# PCB.net
KiCad netlist of a schematic drawn in EasyEDA Pro
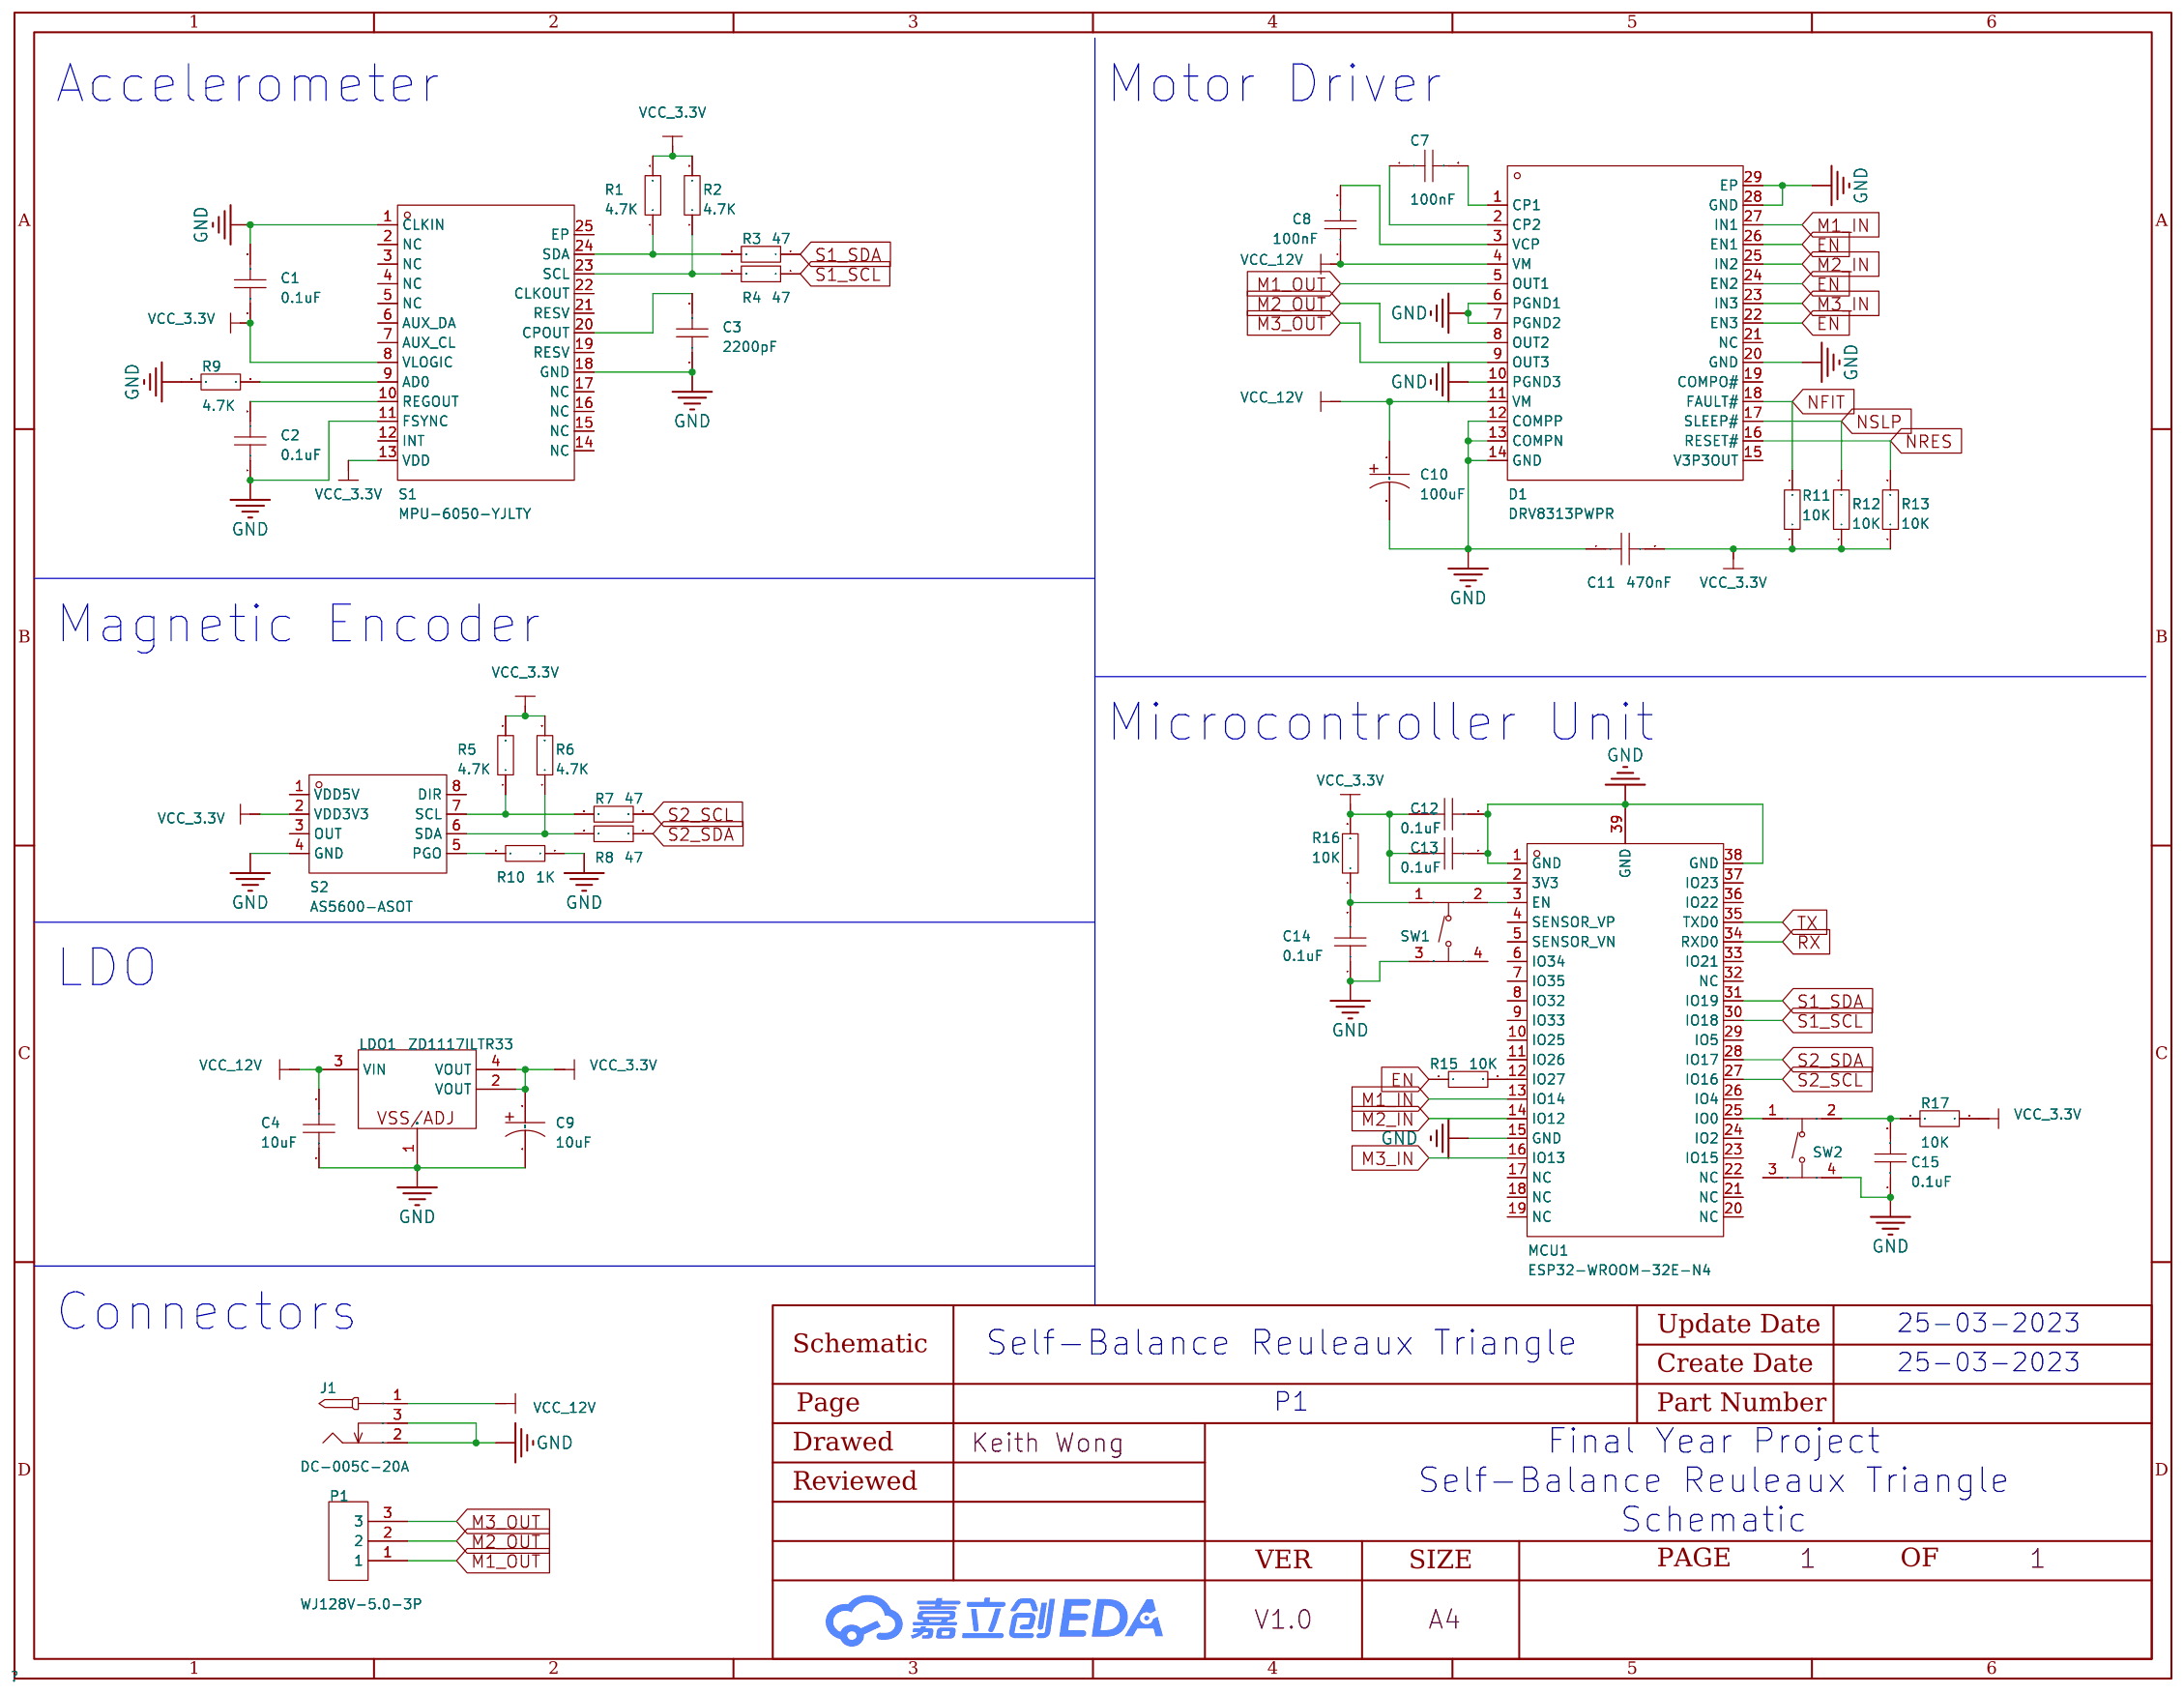
[diagram p0: schematic sheet]

(export (version "E")
  (design (tool "Eeschema 10.0.6"))
  (components
    (comp (ref "C1")
      (value "0.1uF")
      (footprint "easyedapro:C0603")
      (libsource (lib "easyedapro") (part "CapAcitance"))
    )
    (comp (ref "C2")
      (value "0.1uF")
      (footprint "easyedapro:C0603")
      (libsource (lib "easyedapro") (part "CapAcitance"))
    )
    (comp (ref "C3")
      (value "2200pF")
      (footprint "easyedapro:C0603")
      (libsource (lib "easyedapro") (part "CapAcitance"))
    )
    (comp (ref "C4")
      (value "10uF")
      (footprint "easyedapro:C0603")
      (libsource (lib "easyedapro") (part "CapAcitance"))
    )
    (comp (ref "C7")
      (value "100nF")
      (footprint "easyedapro:C0603")
      (libsource (lib "easyedapro") (part "CapAcitance"))
    )
    (comp (ref "C8")
      (value "100nF")
      (footprint "easyedapro:C0603")
      (libsource (lib "easyedapro") (part "CapAcitance"))
    )
    (comp (ref "C9")
      (value "10uF")
      (footprint "easyedapro:CAP-SMD_BD6.3-L6.6-W6.6-FD")
      (libsource (lib "easyedapro") (part "47UF-SMD,6.3*5.4MM"))
    )
    (comp (ref "C10")
      (value "100uF")
      (footprint "easyedapro:CAP-SMD_BD6.3-L6.6-W6.6-FD")
      (libsource (lib "easyedapro") (part "47UF-SMD,6.3*5.4MM"))
    )
    (comp (ref "C11")
      (value "470nF")
      (footprint "easyedapro:C0603")
      (libsource (lib "easyedapro") (part "CapAcitance"))
    )
    (comp (ref "C12")
      (value "0.1uF")
      (footprint "easyedapro:C0603")
      (libsource (lib "easyedapro") (part "CapAcitance"))
    )
    (comp (ref "C13")
      (value "0.1uF")
      (footprint "easyedapro:C0603")
      (libsource (lib "easyedapro") (part "CapAcitance"))
    )
    (comp (ref "C14")
      (value "0.1uF")
      (footprint "easyedapro:C0603")
      (libsource (lib "easyedapro") (part "CapAcitance"))
    )
    (comp (ref "C15")
      (value "0.1uF")
      (footprint "easyedapro:C0603")
      (libsource (lib "easyedapro") (part "CapAcitance"))
    )
    (comp (ref "D1")
      (value "DRV8313PWPR")
      (footprint "easyedapro:HTSSOP-28_L9.8-W4.5-P0.65-LS6.6-BL-EP")
      (description "DRV8313 三路 1/2 H 桥驱动器 IC")
      (fields (field (name "Manufacturer") "TI(德州仪器)"))
      (libsource (lib "easyedapro") (part "DRV8313PWPR"))
    )
    (comp (ref "J1")
      (value "DC-005C-20A")
      (footprint "easyedapro:DC-IN-TH_DC-005C-20A")
      (description "触点内径:2mm;触点外径:6.4mm;额定电流:3A;额定电压:24V;")
      (fields (field (name "Manufacturer") "韩国韩荣"))
      (libsource (lib "easyedapro") (part "DC-005C-20A"))
    )
    (comp (ref "LDO1")
      (value "ZD1117ILTR33")
      (footprint "easyedapro:SOT-223-4_L6.5-W3.5-P2.30-LS7.0-BR")
      (fields (field (name "Manufacturer") "Zetta(澜智)"))
      (libsource (lib "easyedapro") (part "ZD1117ILTR33"))
    )
    (comp (ref "MCU1")
      (value "ESP32-WROOM-32E-N4")
      (footprint "easyedapro:WIFI-SMD_ESP32-WROOM-32E")
      (description "ESP32-WROOM-32E 集成 ESP32-D0WD-V3 芯片，具有?高的稳定性和安全性能。")
      (fields (field (name "Manufacturer") "ESPRESSIF(乐鑫)"))
      (libsource (lib "easyedapro") (part "ESP32-WROOM-32E(4MB)"))
    )
    (comp (ref "P1")
      (value "WJ128V-5.0-3P")
      (footprint "easyedapro:CONN-TH_3P-P5.00_WJ128V-5.0-3P")
      (fields (field (name "Manufacturer") "KANGNEX(康奈克斯电气)"))
      (libsource (lib "easyedapro") (part "WJ128V-5.0-3P"))
    )
    (comp (ref "R1") (value "4.7K") (footprint "easyedapro:R0603") (libsource (lib "easyedapro") (part "电阻")))
    (comp (ref "R2") (value "4.7K") (footprint "easyedapro:R0603") (libsource (lib "easyedapro") (part "电阻")))
    (comp (ref "R3") (value "47") (footprint "easyedapro:R0603") (libsource (lib "easyedapro") (part "电阻")))
    (comp (ref "R4") (value "47") (footprint "easyedapro:R0603") (libsource (lib "easyedapro") (part "电阻")))
    (comp (ref "R5") (value "4.7K") (footprint "easyedapro:R0603") (libsource (lib "easyedapro") (part "电阻")))
    (comp (ref "R6") (value "4.7K") (footprint "easyedapro:R0603") (libsource (lib "easyedapro") (part "电阻")))
    (comp (ref "R7") (value "47") (footprint "easyedapro:R0603") (libsource (lib "easyedapro") (part "电阻")))
    (comp (ref "R8") (value "47") (footprint "easyedapro:R0603") (libsource (lib "easyedapro") (part "电阻")))
    (comp (ref "R9") (value "4.7K") (footprint "easyedapro:R0603") (libsource (lib "easyedapro") (part "电阻")))
    (comp (ref "R10") (value "1K") (footprint "easyedapro:R0603") (libsource (lib "easyedapro") (part "电阻")))
    (comp (ref "R11") (value "10K") (footprint "easyedapro:R0603") (libsource (lib "easyedapro") (part "电阻")))
    (comp (ref "R12") (value "10K") (footprint "easyedapro:R0603") (libsource (lib "easyedapro") (part "电阻")))
    (comp (ref "R13") (value "10K") (footprint "easyedapro:R0603") (libsource (lib "easyedapro") (part "电阻")))
    (comp (ref "R15") (value "10K") (footprint "easyedapro:R0603") (libsource (lib "easyedapro") (part "电阻")))
    (comp (ref "R16") (value "10K") (footprint "easyedapro:R0603") (libsource (lib "easyedapro") (part "电阻")))
    (comp (ref "R17") (value "10K") (footprint "easyedapro:R0603") (libsource (lib "easyedapro") (part "电阻")))
    (comp (ref "S1")
      (value "MPU-6050-YJLTY")
      (footprint "easyedapro:QFN-24_L4.0-W4.0-P0.50-TL-EP2.7")
      (libsource (lib "easyedapro") (part "MPU-6050-YJLTY_C9900004367"))
    )
    (comp (ref "S2")
      (value "AS5600-ASOT")
      (footprint "easyedapro:SOIC-8_L5.0-W4.0-P1.27-LS6.0-BL")
      (fields (field (name "Manufacturer") "ams(艾迈斯半导体)"))
      (libsource (lib "easyedapro") (part "AS5600-ASOT"))
    )
    (comp (ref "SW1")
      (value "TS-1187A-B-A-B")
      (footprint "easyedapro:SW-SMD_4P-L5.1-W5.1-P3.70-LS6.5-TL-2")
      (fields (field (name "Manufacturer") "XKB Connectivity(中国星坤)"))
      (libsource (lib "easyedapro") (part "TS-1187A-B-A-B"))
    )
    (comp (ref "SW2")
      (value "TS-1187A-B-A-B")
      (footprint "easyedapro:SW-SMD_4P-L5.1-W5.1-P3.70-LS6.5-TL-2")
      (fields (field (name "Manufacturer") "XKB Connectivity(中国星坤)"))
      (libsource (lib "easyedapro") (part "TS-1187A-B-A-B"))
    )
  )
  (nets
    (net (code "1") (name "EN") (class "Default")
      (node (ref "D1") (pin "22") (pinfunction "EN3_22") (pintype "input"))
      (node (ref "D1") (pin "24") (pinfunction "EN2_24") (pintype "input"))
      (node (ref "D1") (pin "26") (pinfunction "EN1_26") (pintype "input"))
      (node (ref "R15") (pin "1") (pinfunction "1_1") (pintype "input"))
    )
    (net (code "2") (name "GND") (class "Default")
      (node (ref "C1") (pin "2") (pinfunction "2_2") (pintype "input"))
      (node (ref "C10") (pin "2") (pinfunction "2_2") (pintype "input"))
      (node (ref "C11") (pin "1") (pinfunction "1_1") (pintype "input"))
      (node (ref "C12") (pin "2") (pinfunction "2_2") (pintype "input"))
      (node (ref "C13") (pin "2") (pinfunction "2_2") (pintype "input"))
      (node (ref "C14") (pin "1") (pinfunction "1_1") (pintype "input"))
      (node (ref "C15") (pin "1") (pinfunction "1_1") (pintype "input"))
      (node (ref "C2") (pin "1") (pinfunction "1_1") (pintype "input"))
      (node (ref "C3") (pin "1") (pinfunction "1_1") (pintype "input"))
      (node (ref "C4") (pin "2") (pinfunction "2_2") (pintype "input"))
      (node (ref "C9") (pin "2") (pinfunction "2_2") (pintype "input"))
      (node (ref "D1") (pin "10") (pinfunction "PGND3_10") (pintype "input"))
      (node (ref "D1") (pin "12") (pinfunction "COMPP_12") (pintype "input"))
      (node (ref "D1") (pin "13") (pinfunction "COMPN_13") (pintype "input"))
      (node (ref "D1") (pin "14") (pinfunction "GND_14") (pintype "input"))
      (node (ref "D1") (pin "20") (pinfunction "GND_20") (pintype "input"))
      (node (ref "D1") (pin "28") (pinfunction "GND_28") (pintype "input"))
      (node (ref "D1") (pin "29") (pinfunction "EP_29") (pintype "input"))
      (node (ref "D1") (pin "6") (pinfunction "PGND1_6") (pintype "input"))
      (node (ref "D1") (pin "7") (pinfunction "PGND2_7") (pintype "input"))
      (node (ref "J1") (pin "2") (pinfunction "2_2") (pintype "input"))
      (node (ref "J1") (pin "3") (pinfunction "3_3") (pintype "input"))
      (node (ref "LDO1") (pin "1") (pinfunction "VSS/ADJ_1") (pintype "input"))
      (node (ref "MCU1") (pin "1") (pinfunction "GND_1") (pintype "input"))
      (node (ref "MCU1") (pin "15") (pinfunction "GND_15") (pintype "input"))
      (node (ref "MCU1") (pin "38") (pinfunction "GND_38") (pintype "input"))
      (node (ref "MCU1") (pin "39") (pinfunction "GND_39") (pintype "input"))
      (node (ref "R10") (pin "1") (pinfunction "1_1") (pintype "input"))
      (node (ref "R9") (pin "1") (pinfunction "1_1") (pintype "input"))
      (node (ref "S1") (pin "1") (pinfunction "CLKIN_1") (pintype "input"))
      (node (ref "S1") (pin "11") (pinfunction "FSYNC_11") (pintype "input"))
      (node (ref "S1") (pin "18") (pinfunction "GND_18") (pintype "input"))
      (node (ref "S2") (pin "4") (pinfunction "GND_4") (pintype "input"))
      (node (ref "SW1") (pin "3") (pinfunction "C_3") (pintype "input"))
      (node (ref "SW2") (pin "4") (pinfunction "D_4") (pintype "input"))
    )
    (net (code "3") (name "M1_IN") (class "Default")
      (node (ref "D1") (pin "27") (pinfunction "IN1_27") (pintype "input"))
      (node (ref "MCU1") (pin "13") (pinfunction "IO14_13") (pintype "input"))
    )
    (net (code "4") (name "M1_OUT") (class "Default")
      (node (ref "D1") (pin "5") (pinfunction "OUT1_5") (pintype "input"))
      (node (ref "P1") (pin "1") (pinfunction "1_1") (pintype "input"))
    )
    (net (code "5") (name "M2_IN") (class "Default")
      (node (ref "D1") (pin "25") (pinfunction "IN2_25") (pintype "input"))
      (node (ref "MCU1") (pin "14") (pinfunction "IO12_14") (pintype "input"))
    )
    (net (code "6") (name "M2_OUT") (class "Default")
      (node (ref "D1") (pin "8") (pinfunction "OUT2_8") (pintype "input"))
      (node (ref "P1") (pin "2") (pinfunction "2_2") (pintype "input"))
    )
    (net (code "7") (name "M3_IN") (class "Default")
      (node (ref "D1") (pin "23") (pinfunction "IN3_23") (pintype "input"))
      (node (ref "MCU1") (pin "16") (pinfunction "IO13_16") (pintype "input"))
    )
    (net (code "8") (name "M3_OUT") (class "Default")
      (node (ref "D1") (pin "9") (pinfunction "OUT3_9") (pintype "input"))
      (node (ref "P1") (pin "3") (pinfunction "3_3") (pintype "input"))
    )
    (net (code "9") (name "NFIT") (class "Default")
      (node (ref "D1") (pin "18") (pinfunction "FAULT#_18") (pintype "input"))
      (node (ref "R11") (pin "2") (pinfunction "2_2") (pintype "input"))
    )
    (net (code "10") (name "NRES") (class "Default")
      (node (ref "D1") (pin "16") (pinfunction "RESET#_16") (pintype "input"))
      (node (ref "R13") (pin "2") (pinfunction "2_2") (pintype "input"))
    )
    (net (code "11") (name "NSLP") (class "Default")
      (node (ref "D1") (pin "17") (pinfunction "SLEEP#_17") (pintype "input"))
      (node (ref "R12") (pin "2") (pinfunction "2_2") (pintype "input"))
    )
    (net (code "12") (name "Net-(D1-CP1)") (class "Default")
      (node (ref "C7") (pin "2") (pinfunction "2_2") (pintype "input"))
      (node (ref "D1") (pin "1") (pinfunction "CP1_1") (pintype "input"))
    )
    (net (code "13") (name "Net-(D1-CP2)") (class "Default")
      (node (ref "C7") (pin "1") (pinfunction "1_1") (pintype "input"))
      (node (ref "D1") (pin "2") (pinfunction "CP2_2") (pintype "input"))
    )
    (net (code "14") (name "Net-(D1-VCP)") (class "Default")
      (node (ref "C8") (pin "2") (pinfunction "2_2") (pintype "input"))
      (node (ref "D1") (pin "3") (pinfunction "VCP_3") (pintype "input"))
    )
    (net (code "15") (name "Net-(MCU1-EN)") (class "Default")
      (node (ref "MCU1") (pin "3") (pinfunction "EN_3") (pintype "input"))
      (node (ref "SW1") (pin "2") (pinfunction "B_2") (pintype "input"))
    )
    (net (code "16") (name "Net-(MCU1-IO0)") (class "Default")
      (node (ref "MCU1") (pin "25") (pinfunction "IO0_25") (pintype "input"))
      (node (ref "SW2") (pin "1") (pinfunction "A_1") (pintype "input"))
    )
    (net (code "17") (name "Net-(MCU1-IO27)") (class "Default")
      (node (ref "MCU1") (pin "12") (pinfunction "IO27_12") (pintype "input"))
      (node (ref "R15") (pin "2") (pinfunction "2_2") (pintype "input"))
    )
    (net (code "18") (name "Net-(S1-AD0)") (class "Default")
      (node (ref "R9") (pin "2") (pinfunction "2_2") (pintype "input"))
      (node (ref "S1") (pin "9") (pinfunction "AD0_9") (pintype "input"))
    )
    (net (code "19") (name "Net-(S1-CPOUT)") (class "Default")
      (node (ref "C3") (pin "2") (pinfunction "2_2") (pintype "input"))
      (node (ref "S1") (pin "20") (pinfunction "CPOUT_20") (pintype "input"))
    )
    (net (code "20") (name "Net-(S1-REGOUT)") (class "Default")
      (node (ref "C2") (pin "2") (pinfunction "2_2") (pintype "input"))
      (node (ref "S1") (pin "10") (pinfunction "REGOUT_10") (pintype "input"))
    )
    (net (code "21") (name "Net-(S1-SCL)") (class "Default")
      (node (ref "R2") (pin "1") (pinfunction "1_1") (pintype "input"))
      (node (ref "R4") (pin "2") (pinfunction "2_2") (pintype "input"))
      (node (ref "S1") (pin "23") (pinfunction "SCL_23") (pintype "input"))
    )
    (net (code "22") (name "Net-(S1-SDA)") (class "Default")
      (node (ref "R1") (pin "1") (pinfunction "1_1") (pintype "input"))
      (node (ref "R3") (pin "2") (pinfunction "2_2") (pintype "input"))
      (node (ref "S1") (pin "24") (pinfunction "SDA_24") (pintype "input"))
    )
    (net (code "23") (name "Net-(S2-PGO)") (class "Default")
      (node (ref "R10") (pin "2") (pinfunction "2_2") (pintype "input"))
      (node (ref "S2") (pin "5") (pinfunction "PGO_5") (pintype "input"))
    )
    (net (code "24") (name "Net-(S2-SCL)") (class "Default")
      (node (ref "R5") (pin "1") (pinfunction "1_1") (pintype "input"))
      (node (ref "R7") (pin "2") (pinfunction "2_2") (pintype "input"))
      (node (ref "S2") (pin "7") (pinfunction "SCL_7") (pintype "input"))
    )
    (net (code "25") (name "Net-(S2-SDA)") (class "Default")
      (node (ref "R6") (pin "1") (pinfunction "1_1") (pintype "input"))
      (node (ref "R8") (pin "2") (pinfunction "2_2") (pintype "input"))
      (node (ref "S2") (pin "6") (pinfunction "SDA_6") (pintype "input"))
    )
    (net (code "26") (name "Net-(SW1-A)") (class "Default")
      (node (ref "C14") (pin "2") (pinfunction "2_2") (pintype "input"))
      (node (ref "R16") (pin "1") (pinfunction "1_1") (pintype "input"))
      (node (ref "SW1") (pin "1") (pinfunction "A_1") (pintype "input"))
    )
    (net (code "27") (name "Net-(SW2-B)") (class "Default")
      (node (ref "C15") (pin "2") (pinfunction "2_2") (pintype "input"))
      (node (ref "R17") (pin "1") (pinfunction "1_1") (pintype "input"))
      (node (ref "SW2") (pin "2") (pinfunction "B_2") (pintype "input"))
    )
    (net (code "28") (name "RX") (class "Default")
      (node (ref "MCU1") (pin "34") (pinfunction "RXD0_34") (pintype "input"))
    )
    (net (code "29") (name "S1_SCL") (class "Default")
      (node (ref "MCU1") (pin "30") (pinfunction "IO18_30") (pintype "input"))
      (node (ref "R4") (pin "1") (pinfunction "1_1") (pintype "input"))
    )
    (net (code "30") (name "S1_SDA") (class "Default")
      (node (ref "MCU1") (pin "31") (pinfunction "IO19_31") (pintype "input"))
      (node (ref "R3") (pin "1") (pinfunction "1_1") (pintype "input"))
    )
    (net (code "31") (name "S2_SCL") (class "Default")
      (node (ref "MCU1") (pin "27") (pinfunction "IO16_27") (pintype "input"))
      (node (ref "R7") (pin "1") (pinfunction "1_1") (pintype "input"))
    )
    (net (code "32") (name "S2_SDA") (class "Default")
      (node (ref "MCU1") (pin "28") (pinfunction "IO17_28") (pintype "input"))
      (node (ref "R8") (pin "1") (pinfunction "1_1") (pintype "input"))
    )
    (net (code "33") (name "TX") (class "Default")
      (node (ref "MCU1") (pin "35") (pinfunction "TXD0_35") (pintype "input"))
    )
    (net (code "34") (name "VCC_3.3V") (class "Default")
      (node (ref "C1") (pin "1") (pinfunction "1_1") (pintype "input"))
      (node (ref "C11") (pin "2") (pinfunction "2_2") (pintype "input"))
      (node (ref "C12") (pin "1") (pinfunction "1_1") (pintype "input"))
      (node (ref "C13") (pin "1") (pinfunction "1_1") (pintype "input"))
      (node (ref "C9") (pin "1") (pinfunction "1_1") (pintype "input"))
      (node (ref "LDO1") (pin "2") (pinfunction "VOUT_2") (pintype "input"))
      (node (ref "LDO1") (pin "4") (pinfunction "VOUT_4") (pintype "input"))
      (node (ref "MCU1") (pin "2") (pinfunction "3V3_2") (pintype "input"))
      (node (ref "R1") (pin "2") (pinfunction "2_2") (pintype "input"))
      (node (ref "R11") (pin "1") (pinfunction "1_1") (pintype "input"))
      (node (ref "R12") (pin "1") (pinfunction "1_1") (pintype "input"))
      (node (ref "R13") (pin "1") (pinfunction "1_1") (pintype "input"))
      (node (ref "R16") (pin "2") (pinfunction "2_2") (pintype "input"))
      (node (ref "R17") (pin "2") (pinfunction "2_2") (pintype "input"))
      (node (ref "R2") (pin "2") (pinfunction "2_2") (pintype "input"))
      (node (ref "R5") (pin "2") (pinfunction "2_2") (pintype "input"))
      (node (ref "R6") (pin "2") (pinfunction "2_2") (pintype "input"))
      (node (ref "S1") (pin "13") (pinfunction "VDD_13") (pintype "input"))
      (node (ref "S1") (pin "8") (pinfunction "VLOGIC_8") (pintype "input"))
      (node (ref "S2") (pin "2") (pinfunction "VDD3V3_2") (pintype "input"))
    )
    (net (code "35") (name "VCC_12V") (class "Default")
      (node (ref "C10") (pin "1") (pinfunction "1_1") (pintype "input"))
      (node (ref "C4") (pin "1") (pinfunction "1_1") (pintype "input"))
      (node (ref "C8") (pin "1") (pinfunction "1_1") (pintype "input"))
      (node (ref "D1") (pin "11") (pinfunction "VM_11") (pintype "input"))
      (node (ref "D1") (pin "4") (pinfunction "VM_4") (pintype "input"))
      (node (ref "J1") (pin "1") (pinfunction "1_1") (pintype "input"))
      (node (ref "LDO1") (pin "3") (pinfunction "VIN_3") (pintype "input"))
    )
    (net (code "36") (name "unconnected-(D1-COMPO#-Pad19)") (class "Default")
      (node (ref "D1") (pin "19") (pinfunction "COMPO#_19") (pintype "input"))
    )
    (net (code "37") (name "unconnected-(D1-NC-Pad21)") (class "Default")
      (node (ref "D1") (pin "21") (pinfunction "NC_21") (pintype "input"))
    )
    (net (code "38") (name "unconnected-(D1-V3P3OUT-Pad15)") (class "Default")
      (node (ref "D1") (pin "15") (pinfunction "V3P3OUT_15") (pintype "input"))
    )
    (net (code "39") (name "unconnected-(MCU1-IO2-Pad24)") (class "Default")
      (node (ref "MCU1") (pin "24") (pinfunction "IO2_24") (pintype "input"))
    )
    (net (code "40") (name "unconnected-(MCU1-IO4-Pad26)") (class "Default")
      (node (ref "MCU1") (pin "26") (pinfunction "IO4_26") (pintype "input"))
    )
    (net (code "41") (name "unconnected-(MCU1-IO5-Pad29)") (class "Default")
      (node (ref "MCU1") (pin "29") (pinfunction "IO5_29") (pintype "input"))
    )
    (net (code "42") (name "unconnected-(MCU1-IO15-Pad23)") (class "Default")
      (node (ref "MCU1") (pin "23") (pinfunction "IO15_23") (pintype "input"))
    )
    (net (code "43") (name "unconnected-(MCU1-IO21-Pad33)") (class "Default")
      (node (ref "MCU1") (pin "33") (pinfunction "IO21_33") (pintype "input"))
    )
    (net (code "44") (name "unconnected-(MCU1-IO22-Pad36)") (class "Default")
      (node (ref "MCU1") (pin "36") (pinfunction "IO22_36") (pintype "input"))
    )
    (net (code "45") (name "unconnected-(MCU1-IO23-Pad37)") (class "Default")
      (node (ref "MCU1") (pin "37") (pinfunction "IO23_37") (pintype "input"))
    )
    (net (code "46") (name "unconnected-(MCU1-IO25-Pad10)") (class "Default")
      (node (ref "MCU1") (pin "10") (pinfunction "IO25_10") (pintype "input"))
    )
    (net (code "47") (name "unconnected-(MCU1-IO26-Pad11)") (class "Default")
      (node (ref "MCU1") (pin "11") (pinfunction "IO26_11") (pintype "input"))
    )
    (net (code "48") (name "unconnected-(MCU1-IO32-Pad8)") (class "Default")
      (node (ref "MCU1") (pin "8") (pinfunction "IO32_8") (pintype "input"))
    )
    (net (code "49") (name "unconnected-(MCU1-IO33-Pad9)") (class "Default")
      (node (ref "MCU1") (pin "9") (pinfunction "IO33_9") (pintype "input"))
    )
    (net (code "50") (name "unconnected-(MCU1-IO34-Pad6)") (class "Default")
      (node (ref "MCU1") (pin "6") (pinfunction "IO34_6") (pintype "input"))
    )
    (net (code "51") (name "unconnected-(MCU1-IO35-Pad7)") (class "Default")
      (node (ref "MCU1") (pin "7") (pinfunction "IO35_7") (pintype "input"))
    )
    (net (code "52") (name "unconnected-(MCU1-NC-Pad17)") (class "Default")
      (node (ref "MCU1") (pin "17") (pinfunction "NC_17") (pintype "input"))
    )
    (net (code "53") (name "unconnected-(MCU1-NC-Pad18)") (class "Default")
      (node (ref "MCU1") (pin "18") (pinfunction "NC_18") (pintype "input"))
    )
    (net (code "54") (name "unconnected-(MCU1-NC-Pad19)") (class "Default")
      (node (ref "MCU1") (pin "19") (pinfunction "NC_19") (pintype "input"))
    )
    (net (code "55") (name "unconnected-(MCU1-NC-Pad20)") (class "Default")
      (node (ref "MCU1") (pin "20") (pinfunction "NC_20") (pintype "input"))
    )
    (net (code "56") (name "unconnected-(MCU1-NC-Pad21)") (class "Default")
      (node (ref "MCU1") (pin "21") (pinfunction "NC_21") (pintype "input"))
    )
    (net (code "57") (name "unconnected-(MCU1-NC-Pad22)") (class "Default")
      (node (ref "MCU1") (pin "22") (pinfunction "NC_22") (pintype "input"))
    )
    (net (code "58") (name "unconnected-(MCU1-NC-Pad32)") (class "Default")
      (node (ref "MCU1") (pin "32") (pinfunction "NC_32") (pintype "input"))
    )
    (net (code "59") (name "unconnected-(MCU1-SENSOR_VN-Pad5)") (class "Default")
      (node (ref "MCU1") (pin "5") (pinfunction "SENSOR_VN_5") (pintype "input"))
    )
    (net (code "60") (name "unconnected-(MCU1-SENSOR_VP-Pad4)") (class "Default")
      (node (ref "MCU1") (pin "4") (pinfunction "SENSOR_VP_4") (pintype "input"))
    )
    (net (code "61") (name "unconnected-(S1-AUX_CL-Pad7)") (class "Default")
      (node (ref "S1") (pin "7") (pinfunction "AUX_CL_7") (pintype "input"))
    )
    (net (code "62") (name "unconnected-(S1-AUX_DA-Pad6)") (class "Default")
      (node (ref "S1") (pin "6") (pinfunction "AUX_DA_6") (pintype "input"))
    )
    (net (code "63") (name "unconnected-(S1-CLKOUT-Pad22)") (class "Default")
      (node (ref "S1") (pin "22") (pinfunction "CLKOUT_22") (pintype "input"))
    )
    (net (code "64") (name "unconnected-(S1-EP-Pad25)") (class "Default")
      (node (ref "S1") (pin "25") (pinfunction "EP_25") (pintype "input"))
    )
    (net (code "65") (name "unconnected-(S1-INT-Pad12)") (class "Default")
      (node (ref "S1") (pin "12") (pinfunction "INT_12") (pintype "input"))
    )
    (net (code "66") (name "unconnected-(S1-NC-Pad2)") (class "Default")
      (node (ref "S1") (pin "2") (pinfunction "NC_2") (pintype "input"))
    )
    (net (code "67") (name "unconnected-(S1-NC-Pad3)") (class "Default")
      (node (ref "S1") (pin "3") (pinfunction "NC_3") (pintype "input"))
    )
    (net (code "68") (name "unconnected-(S1-NC-Pad4)") (class "Default")
      (node (ref "S1") (pin "4") (pinfunction "NC_4") (pintype "input"))
    )
    (net (code "69") (name "unconnected-(S1-NC-Pad5)") (class "Default")
      (node (ref "S1") (pin "5") (pinfunction "NC_5") (pintype "input"))
    )
    (net (code "70") (name "unconnected-(S1-NC-Pad14)") (class "Default")
      (node (ref "S1") (pin "14") (pinfunction "NC_14") (pintype "input"))
    )
    (net (code "71") (name "unconnected-(S1-NC-Pad15)") (class "Default")
      (node (ref "S1") (pin "15") (pinfunction "NC_15") (pintype "input"))
    )
    (net (code "72") (name "unconnected-(S1-NC-Pad16)") (class "Default")
      (node (ref "S1") (pin "16") (pinfunction "NC_16") (pintype "input"))
    )
    (net (code "73") (name "unconnected-(S1-NC-Pad17)") (class "Default")
      (node (ref "S1") (pin "17") (pinfunction "NC_17") (pintype "input"))
    )
    (net (code "74") (name "unconnected-(S1-RESV-Pad19)") (class "Default")
      (node (ref "S1") (pin "19") (pinfunction "RESV_19") (pintype "input"))
    )
    (net (code "75") (name "unconnected-(S1-RESV-Pad21)") (class "Default")
      (node (ref "S1") (pin "21") (pinfunction "RESV_21") (pintype "input"))
    )
    (net (code "76") (name "unconnected-(S2-DIR-Pad8)") (class "Default")
      (node (ref "S2") (pin "8") (pinfunction "DIR_8") (pintype "input"))
    )
    (net (code "77") (name "unconnected-(S2-OUT-Pad3)") (class "Default")
      (node (ref "S2") (pin "3") (pinfunction "OUT_3") (pintype "input"))
    )
    (net (code "78") (name "unconnected-(S2-VDD5V-Pad1)") (class "Default")
      (node (ref "S2") (pin "1") (pinfunction "VDD5V_1") (pintype "input"))
    )
    (net (code "79") (name "unconnected-(SW1-D-Pad4)") (class "Default")
      (node (ref "SW1") (pin "4") (pinfunction "D_4") (pintype "input"))
    )
    (net (code "80") (name "unconnected-(SW2-C-Pad3)") (class "Default")
      (node (ref "SW2") (pin "3") (pinfunction "C_3") (pintype "input"))
    )
  )
)
